# touch.net
KiCad netlist of a schematic drawn in Altium Designer
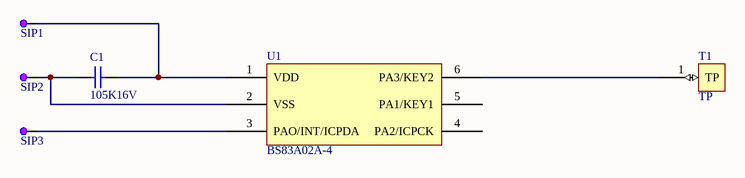
[diagram p0: touch.SchDoc]

(export (version "E")
  (design (tool "Eeschema 10.0.6"))
  (components
    (comp (ref "C1")
      (value "105K16V")
      (footprint "C0603")
      (description "贴片电容-陶瓷")
      (libsource (lib "AIWAC-bolsterV01") (part "C0603X7R-105K16V"))
    )
    (comp (ref "SIP1")
      (value "SIP1")
      (footprint "SIP-2MM")
      (description "单排排针，2.54mm针距，1P,针总长11.1mm,黑色")
      (libsource (lib "标准通用原理图库") (part "SIP1"))
    )
    (comp (ref "SIP2")
      (value "SIP1")
      (footprint "SIP-2MM")
      (description "单排排针，2.54mm针距，1P,针总长11.1mm,黑色")
      (libsource (lib "标准通用原理图库") (part "SIP1"))
    )
    (comp (ref "SIP3")
      (value "SIP1")
      (footprint "SIP-2MM")
      (description "单排排针，2.54mm针距，1P,针总长11.1mm,黑色")
      (libsource (lib "标准通用原理图库") (part "SIP1"))
    )
    (comp (ref "T1") (value "TP") (footprint "touch 按键") (libsource (lib "AIWAC-bolsterV01") (part "TP")))
    (comp (ref "U1")
      (value "BS83A02A-4")
      (footprint "U-SOT-23-6")
      (libsource (lib "AIWAC-bolsterV01") (part "BS83A02A-4"))
    )
  )
  (nets
    (net (code "1") (name "Net-(T1-TP)") (class "Default")
      (node (ref "T1") (pin "1") (pinfunction "TP_1") (pintype "bidirectional"))
      (node (ref "U1") (pin "6") (pinfunction "PA3/KEY2_6") (pintype "passive"))
    )
    (net (code "2") (name "Net-(U1-PAO{slash}INT{slash}ICPDA)") (class "Default")
      (node (ref "SIP3") (pin "1") (pinfunction "1_1") (pintype "passive"))
      (node (ref "U1") (pin "3") (pinfunction "PAO/INT/ICPDA_3") (pintype "passive"))
    )
    (net (code "3") (name "Net-(U1-VDD)") (class "Default")
      (node (ref "C1") (pin "1") (pinfunction "1_1") (pintype "passive"))
      (node (ref "SIP1") (pin "1") (pinfunction "1_1") (pintype "passive"))
      (node (ref "U1") (pin "1") (pinfunction "VDD_1") (pintype "passive"))
    )
    (net (code "4") (name "Net-(U1-VSS)") (class "Default")
      (node (ref "C1") (pin "2") (pinfunction "2_2") (pintype "passive"))
      (node (ref "SIP2") (pin "1") (pinfunction "1_1") (pintype "passive"))
      (node (ref "U1") (pin "2") (pinfunction "VSS_2") (pintype "passive"))
    )
    (net (code "5") (name "unconnected-(U1-PA1{slash}KEY1-Pad5)") (class "Default")
      (node (ref "U1") (pin "5") (pinfunction "PA1/KEY1_5") (pintype "passive"))
    )
    (net (code "6") (name "unconnected-(U1-PA2{slash}ICPCK-Pad4)") (class "Default")
      (node (ref "U1") (pin "4") (pinfunction "PA2/ICPCK_4") (pintype "passive"))
    )
  )
)
